# pb-led-matrix.net
KiCad netlist of a schematic drawn in EAGLE
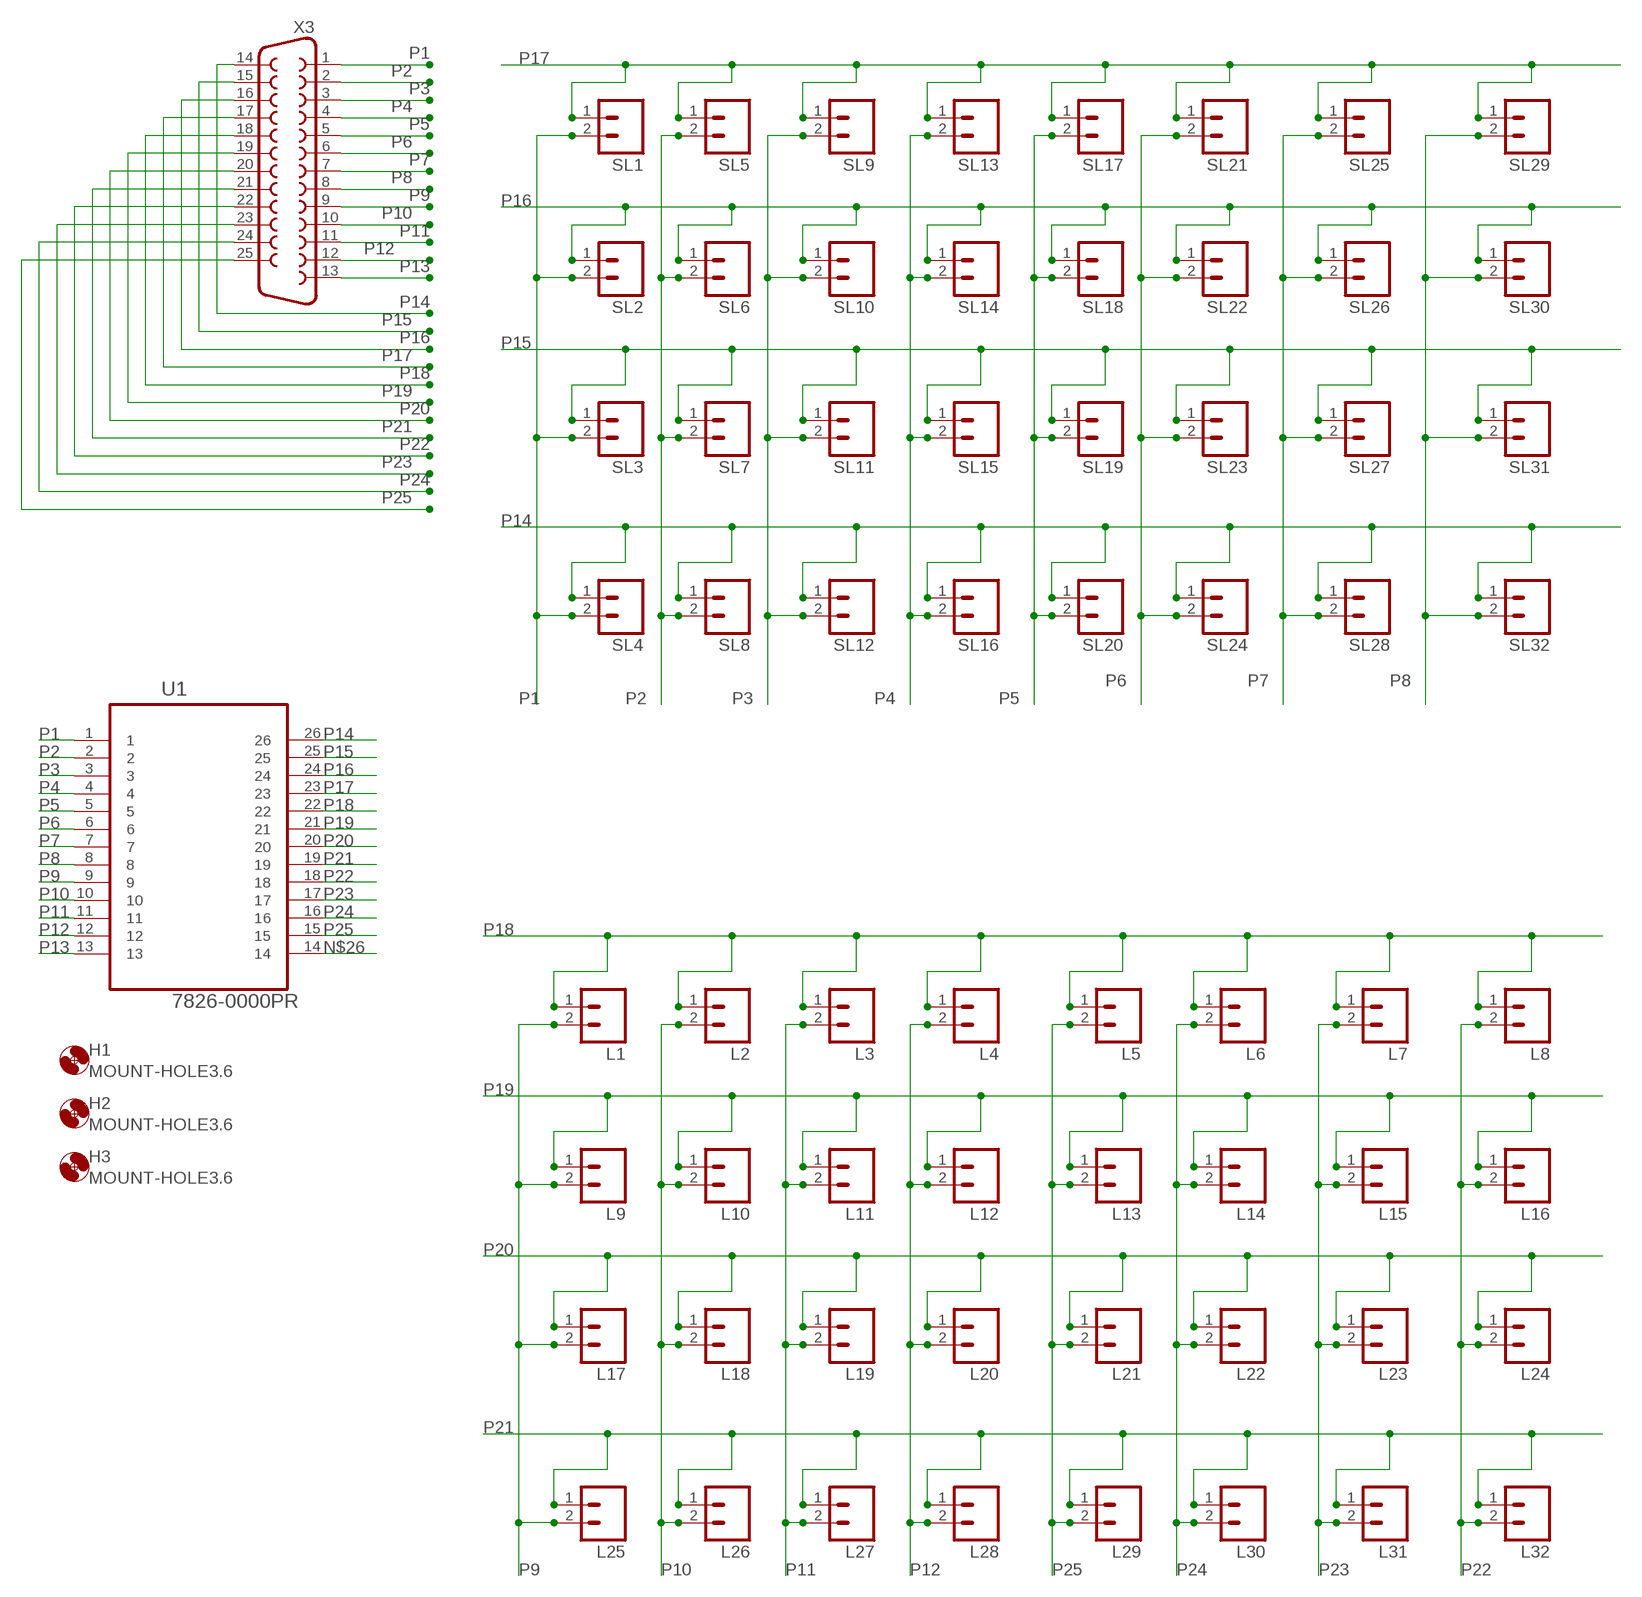
[diagram p0: schematic, sheet 1]

(export (version "E")
  (design (tool "Eeschema 10.0.6"))
  (components
    (comp (ref "H1")
      (value "MOUNT-HOLE3.6")
      (footprint "eagle-import:3,6")
      (libsource (lib "eagle-import") (part "MOUNT-HOLE3.6"))
    )
    (comp (ref "H2")
      (value "MOUNT-HOLE3.6")
      (footprint "eagle-import:3,6")
      (libsource (lib "eagle-import") (part "MOUNT-HOLE3.6"))
    )
    (comp (ref "H3")
      (value "MOUNT-HOLE3.6")
      (footprint "eagle-import:3,6")
      (libsource (lib "eagle-import") (part "MOUNT-HOLE3.6"))
    )
    (comp (ref "L1")
      (value "M02")
      (footprint "eagle-import:02P")
      (libsource (lib "eagle-import") (part "M02"))
    )
    (comp (ref "L2")
      (value "M02")
      (footprint "eagle-import:02P")
      (libsource (lib "eagle-import") (part "M02"))
    )
    (comp (ref "L3")
      (value "M02")
      (footprint "eagle-import:02P")
      (libsource (lib "eagle-import") (part "M02"))
    )
    (comp (ref "L4")
      (value "M02")
      (footprint "eagle-import:02P")
      (libsource (lib "eagle-import") (part "M02"))
    )
    (comp (ref "L5")
      (value "M02")
      (footprint "eagle-import:02P")
      (libsource (lib "eagle-import") (part "M02"))
    )
    (comp (ref "L6")
      (value "M02")
      (footprint "eagle-import:02P")
      (libsource (lib "eagle-import") (part "M02"))
    )
    (comp (ref "L7")
      (value "M02")
      (footprint "eagle-import:02P")
      (libsource (lib "eagle-import") (part "M02"))
    )
    (comp (ref "L8")
      (value "M02")
      (footprint "eagle-import:02P")
      (libsource (lib "eagle-import") (part "M02"))
    )
    (comp (ref "L9")
      (value "M02")
      (footprint "eagle-import:02P")
      (libsource (lib "eagle-import") (part "M02"))
    )
    (comp (ref "L10")
      (value "M02")
      (footprint "eagle-import:02P")
      (libsource (lib "eagle-import") (part "M02"))
    )
    (comp (ref "L11")
      (value "M02")
      (footprint "eagle-import:02P")
      (libsource (lib "eagle-import") (part "M02"))
    )
    (comp (ref "L12")
      (value "M02")
      (footprint "eagle-import:02P")
      (libsource (lib "eagle-import") (part "M02"))
    )
    (comp (ref "L13")
      (value "M02")
      (footprint "eagle-import:02P")
      (libsource (lib "eagle-import") (part "M02"))
    )
    (comp (ref "L14")
      (value "M02")
      (footprint "eagle-import:02P")
      (libsource (lib "eagle-import") (part "M02"))
    )
    (comp (ref "L15")
      (value "M02")
      (footprint "eagle-import:02P")
      (libsource (lib "eagle-import") (part "M02"))
    )
    (comp (ref "L16")
      (value "M02")
      (footprint "eagle-import:02P")
      (libsource (lib "eagle-import") (part "M02"))
    )
    (comp (ref "L17")
      (value "M02")
      (footprint "eagle-import:02P")
      (libsource (lib "eagle-import") (part "M02"))
    )
    (comp (ref "L18")
      (value "M02")
      (footprint "eagle-import:02P")
      (libsource (lib "eagle-import") (part "M02"))
    )
    (comp (ref "L19")
      (value "M02")
      (footprint "eagle-import:02P")
      (libsource (lib "eagle-import") (part "M02"))
    )
    (comp (ref "L20")
      (value "M02")
      (footprint "eagle-import:02P")
      (libsource (lib "eagle-import") (part "M02"))
    )
    (comp (ref "L21")
      (value "M02")
      (footprint "eagle-import:02P")
      (libsource (lib "eagle-import") (part "M02"))
    )
    (comp (ref "L22")
      (value "M02")
      (footprint "eagle-import:02P")
      (libsource (lib "eagle-import") (part "M02"))
    )
    (comp (ref "L23")
      (value "M02")
      (footprint "eagle-import:02P")
      (libsource (lib "eagle-import") (part "M02"))
    )
    (comp (ref "L24")
      (value "M02")
      (footprint "eagle-import:02P")
      (libsource (lib "eagle-import") (part "M02"))
    )
    (comp (ref "L25")
      (value "M02")
      (footprint "eagle-import:02P")
      (libsource (lib "eagle-import") (part "M02"))
    )
    (comp (ref "L26")
      (value "M02")
      (footprint "eagle-import:02P")
      (libsource (lib "eagle-import") (part "M02"))
    )
    (comp (ref "L27")
      (value "M02")
      (footprint "eagle-import:02P")
      (libsource (lib "eagle-import") (part "M02"))
    )
    (comp (ref "L28")
      (value "M02")
      (footprint "eagle-import:02P")
      (libsource (lib "eagle-import") (part "M02"))
    )
    (comp (ref "L29")
      (value "M02")
      (footprint "eagle-import:02P")
      (libsource (lib "eagle-import") (part "M02"))
    )
    (comp (ref "L30")
      (value "M02")
      (footprint "eagle-import:02P")
      (libsource (lib "eagle-import") (part "M02"))
    )
    (comp (ref "L31")
      (value "M02")
      (footprint "eagle-import:02P")
      (libsource (lib "eagle-import") (part "M02"))
    )
    (comp (ref "L32")
      (value "M02")
      (footprint "eagle-import:02P")
      (libsource (lib "eagle-import") (part "M02"))
    )
    (comp (ref "SL1")
      (value "M02")
      (footprint "eagle-import:02P")
      (libsource (lib "eagle-import") (part "M02"))
    )
    (comp (ref "SL2")
      (value "M02")
      (footprint "eagle-import:02P")
      (libsource (lib "eagle-import") (part "M02"))
    )
    (comp (ref "SL3")
      (value "M02")
      (footprint "eagle-import:02P")
      (libsource (lib "eagle-import") (part "M02"))
    )
    (comp (ref "SL4")
      (value "M02")
      (footprint "eagle-import:02P")
      (libsource (lib "eagle-import") (part "M02"))
    )
    (comp (ref "SL5")
      (value "M02")
      (footprint "eagle-import:02P")
      (libsource (lib "eagle-import") (part "M02"))
    )
    (comp (ref "SL6")
      (value "M02")
      (footprint "eagle-import:02P")
      (libsource (lib "eagle-import") (part "M02"))
    )
    (comp (ref "SL7")
      (value "M02")
      (footprint "eagle-import:02P")
      (libsource (lib "eagle-import") (part "M02"))
    )
    (comp (ref "SL8")
      (value "M02")
      (footprint "eagle-import:02P")
      (libsource (lib "eagle-import") (part "M02"))
    )
    (comp (ref "SL9")
      (value "M02")
      (footprint "eagle-import:02P")
      (libsource (lib "eagle-import") (part "M02"))
    )
    (comp (ref "SL10")
      (value "M02")
      (footprint "eagle-import:02P")
      (libsource (lib "eagle-import") (part "M02"))
    )
    (comp (ref "SL11")
      (value "M02")
      (footprint "eagle-import:02P")
      (libsource (lib "eagle-import") (part "M02"))
    )
    (comp (ref "SL12")
      (value "M02")
      (footprint "eagle-import:02P")
      (libsource (lib "eagle-import") (part "M02"))
    )
    (comp (ref "SL13")
      (value "M02")
      (footprint "eagle-import:02P")
      (libsource (lib "eagle-import") (part "M02"))
    )
    (comp (ref "SL14")
      (value "M02")
      (footprint "eagle-import:02P")
      (libsource (lib "eagle-import") (part "M02"))
    )
    (comp (ref "SL15")
      (value "M02")
      (footprint "eagle-import:02P")
      (libsource (lib "eagle-import") (part "M02"))
    )
    (comp (ref "SL16")
      (value "M02")
      (footprint "eagle-import:02P")
      (libsource (lib "eagle-import") (part "M02"))
    )
    (comp (ref "SL17")
      (value "M02")
      (footprint "eagle-import:02P")
      (libsource (lib "eagle-import") (part "M02"))
    )
    (comp (ref "SL18")
      (value "M02")
      (footprint "eagle-import:02P")
      (libsource (lib "eagle-import") (part "M02"))
    )
    (comp (ref "SL19")
      (value "M02")
      (footprint "eagle-import:02P")
      (libsource (lib "eagle-import") (part "M02"))
    )
    (comp (ref "SL20")
      (value "M02")
      (footprint "eagle-import:02P")
      (libsource (lib "eagle-import") (part "M02"))
    )
    (comp (ref "SL21")
      (value "M02")
      (footprint "eagle-import:02P")
      (libsource (lib "eagle-import") (part "M02"))
    )
    (comp (ref "SL22")
      (value "M02")
      (footprint "eagle-import:02P")
      (libsource (lib "eagle-import") (part "M02"))
    )
    (comp (ref "SL23")
      (value "M02")
      (footprint "eagle-import:02P")
      (libsource (lib "eagle-import") (part "M02"))
    )
    (comp (ref "SL24")
      (value "M02")
      (footprint "eagle-import:02P")
      (libsource (lib "eagle-import") (part "M02"))
    )
    (comp (ref "SL25")
      (value "M02")
      (footprint "eagle-import:02P")
      (libsource (lib "eagle-import") (part "M02"))
    )
    (comp (ref "SL26")
      (value "M02")
      (footprint "eagle-import:02P")
      (libsource (lib "eagle-import") (part "M02"))
    )
    (comp (ref "SL27")
      (value "M02")
      (footprint "eagle-import:02P")
      (libsource (lib "eagle-import") (part "M02"))
    )
    (comp (ref "SL28")
      (value "M02")
      (footprint "eagle-import:02P")
      (libsource (lib "eagle-import") (part "M02"))
    )
    (comp (ref "SL29")
      (value "M02")
      (footprint "eagle-import:02P")
      (libsource (lib "eagle-import") (part "M02"))
    )
    (comp (ref "SL30")
      (value "M02")
      (footprint "eagle-import:02P")
      (libsource (lib "eagle-import") (part "M02"))
    )
    (comp (ref "SL31")
      (value "M02")
      (footprint "eagle-import:02P")
      (libsource (lib "eagle-import") (part "M02"))
    )
    (comp (ref "SL32")
      (value "M02")
      (footprint "eagle-import:02P")
      (libsource (lib "eagle-import") (part "M02"))
    )
    (comp (ref "U1")
      (value "7826-0000PR")
      (footprint "eagle-import:3M_7826-0000PR")
      (libsource (lib "eagle-import") (part "7826-0000PR"))
    )
    (comp (ref "X3")
      (value "F25VP")
      (footprint "eagle-import:F25VP")
      (libsource (lib "eagle-import") (part "F25VP"))
    )
  )
  (nets
    (net (code "1") (name "/N$26") (class "Default")
      (node (ref "U1") (pin "14") (pinfunction "14_14") (pintype "passive"))
    )
    (net (code "2") (name "/P1") (class "Default")
      (node (ref "SL1") (pin "2") (pinfunction "2_2") (pintype "passive"))
      (node (ref "SL2") (pin "2") (pinfunction "2_2") (pintype "passive"))
      (node (ref "SL3") (pin "2") (pinfunction "2_2") (pintype "passive"))
      (node (ref "SL4") (pin "2") (pinfunction "2_2") (pintype "passive"))
      (node (ref "U1") (pin "1") (pinfunction "1_1") (pintype "passive"))
      (node (ref "X3") (pin "1") (pinfunction "1_1") (pintype "passive"))
    )
    (net (code "3") (name "/P2") (class "Default")
      (node (ref "SL5") (pin "2") (pinfunction "2_2") (pintype "passive"))
      (node (ref "SL6") (pin "2") (pinfunction "2_2") (pintype "passive"))
      (node (ref "SL7") (pin "2") (pinfunction "2_2") (pintype "passive"))
      (node (ref "SL8") (pin "2") (pinfunction "2_2") (pintype "passive"))
      (node (ref "U1") (pin "2") (pinfunction "2_2") (pintype "passive"))
      (node (ref "X3") (pin "2") (pinfunction "2_2") (pintype "passive"))
    )
    (net (code "4") (name "/P3") (class "Default")
      (node (ref "SL10") (pin "2") (pinfunction "2_2") (pintype "passive"))
      (node (ref "SL11") (pin "2") (pinfunction "2_2") (pintype "passive"))
      (node (ref "SL12") (pin "2") (pinfunction "2_2") (pintype "passive"))
      (node (ref "SL9") (pin "2") (pinfunction "2_2") (pintype "passive"))
      (node (ref "U1") (pin "3") (pinfunction "3_3") (pintype "passive"))
      (node (ref "X3") (pin "3") (pinfunction "3_3") (pintype "passive"))
    )
    (net (code "5") (name "/P4") (class "Default")
      (node (ref "SL13") (pin "2") (pinfunction "2_2") (pintype "passive"))
      (node (ref "SL14") (pin "2") (pinfunction "2_2") (pintype "passive"))
      (node (ref "SL15") (pin "2") (pinfunction "2_2") (pintype "passive"))
      (node (ref "SL16") (pin "2") (pinfunction "2_2") (pintype "passive"))
      (node (ref "U1") (pin "4") (pinfunction "4_4") (pintype "passive"))
      (node (ref "X3") (pin "4") (pinfunction "4_4") (pintype "passive"))
    )
    (net (code "6") (name "/P5") (class "Default")
      (node (ref "SL17") (pin "2") (pinfunction "2_2") (pintype "passive"))
      (node (ref "SL18") (pin "2") (pinfunction "2_2") (pintype "passive"))
      (node (ref "SL19") (pin "2") (pinfunction "2_2") (pintype "passive"))
      (node (ref "SL20") (pin "2") (pinfunction "2_2") (pintype "passive"))
      (node (ref "U1") (pin "5") (pinfunction "5_5") (pintype "passive"))
      (node (ref "X3") (pin "5") (pinfunction "5_5") (pintype "passive"))
    )
    (net (code "7") (name "/P6") (class "Default")
      (node (ref "SL21") (pin "2") (pinfunction "2_2") (pintype "passive"))
      (node (ref "SL22") (pin "2") (pinfunction "2_2") (pintype "passive"))
      (node (ref "SL23") (pin "2") (pinfunction "2_2") (pintype "passive"))
      (node (ref "SL24") (pin "2") (pinfunction "2_2") (pintype "passive"))
      (node (ref "U1") (pin "6") (pinfunction "6_6") (pintype "passive"))
      (node (ref "X3") (pin "6") (pinfunction "6_6") (pintype "passive"))
    )
    (net (code "8") (name "/P7") (class "Default")
      (node (ref "SL25") (pin "2") (pinfunction "2_2") (pintype "passive"))
      (node (ref "SL26") (pin "2") (pinfunction "2_2") (pintype "passive"))
      (node (ref "SL27") (pin "2") (pinfunction "2_2") (pintype "passive"))
      (node (ref "SL28") (pin "2") (pinfunction "2_2") (pintype "passive"))
      (node (ref "U1") (pin "7") (pinfunction "7_7") (pintype "passive"))
      (node (ref "X3") (pin "7") (pinfunction "7_7") (pintype "passive"))
    )
    (net (code "9") (name "/P8") (class "Default")
      (node (ref "SL29") (pin "2") (pinfunction "2_2") (pintype "passive"))
      (node (ref "SL30") (pin "2") (pinfunction "2_2") (pintype "passive"))
      (node (ref "SL31") (pin "2") (pinfunction "2_2") (pintype "passive"))
      (node (ref "SL32") (pin "2") (pinfunction "2_2") (pintype "passive"))
      (node (ref "U1") (pin "8") (pinfunction "8_8") (pintype "passive"))
      (node (ref "X3") (pin "8") (pinfunction "8_8") (pintype "passive"))
    )
    (net (code "10") (name "/P9") (class "Default")
      (node (ref "L1") (pin "2") (pinfunction "2_2") (pintype "passive"))
      (node (ref "L17") (pin "2") (pinfunction "2_2") (pintype "passive"))
      (node (ref "L25") (pin "2") (pinfunction "2_2") (pintype "passive"))
      (node (ref "L9") (pin "2") (pinfunction "2_2") (pintype "passive"))
      (node (ref "U1") (pin "9") (pinfunction "9_9") (pintype "passive"))
      (node (ref "X3") (pin "9") (pinfunction "9_9") (pintype "passive"))
    )
    (net (code "11") (name "/P10") (class "Default")
      (node (ref "L10") (pin "2") (pinfunction "2_2") (pintype "passive"))
      (node (ref "L18") (pin "2") (pinfunction "2_2") (pintype "passive"))
      (node (ref "L2") (pin "2") (pinfunction "2_2") (pintype "passive"))
      (node (ref "L26") (pin "2") (pinfunction "2_2") (pintype "passive"))
      (node (ref "U1") (pin "10") (pinfunction "10_10") (pintype "passive"))
      (node (ref "X3") (pin "10") (pinfunction "10_10") (pintype "passive"))
    )
    (net (code "12") (name "/P11") (class "Default")
      (node (ref "L11") (pin "2") (pinfunction "2_2") (pintype "passive"))
      (node (ref "L19") (pin "2") (pinfunction "2_2") (pintype "passive"))
      (node (ref "L27") (pin "2") (pinfunction "2_2") (pintype "passive"))
      (node (ref "L3") (pin "2") (pinfunction "2_2") (pintype "passive"))
      (node (ref "U1") (pin "11") (pinfunction "11_11") (pintype "passive"))
      (node (ref "X3") (pin "11") (pinfunction "11_11") (pintype "passive"))
    )
    (net (code "13") (name "/P12") (class "Default")
      (node (ref "L12") (pin "2") (pinfunction "2_2") (pintype "passive"))
      (node (ref "L20") (pin "2") (pinfunction "2_2") (pintype "passive"))
      (node (ref "L28") (pin "2") (pinfunction "2_2") (pintype "passive"))
      (node (ref "L4") (pin "2") (pinfunction "2_2") (pintype "passive"))
      (node (ref "U1") (pin "12") (pinfunction "12_12") (pintype "passive"))
      (node (ref "X3") (pin "12") (pinfunction "12_12") (pintype "passive"))
    )
    (net (code "14") (name "/P13") (class "Default")
      (node (ref "U1") (pin "13") (pinfunction "13_13") (pintype "passive"))
      (node (ref "X3") (pin "13") (pinfunction "13_13") (pintype "passive"))
    )
    (net (code "15") (name "/P14") (class "Default")
      (node (ref "SL12") (pin "1") (pinfunction "1_1") (pintype "passive"))
      (node (ref "SL16") (pin "1") (pinfunction "1_1") (pintype "passive"))
      (node (ref "SL20") (pin "1") (pinfunction "1_1") (pintype "passive"))
      (node (ref "SL24") (pin "1") (pinfunction "1_1") (pintype "passive"))
      (node (ref "SL28") (pin "1") (pinfunction "1_1") (pintype "passive"))
      (node (ref "SL32") (pin "1") (pinfunction "1_1") (pintype "passive"))
      (node (ref "SL4") (pin "1") (pinfunction "1_1") (pintype "passive"))
      (node (ref "SL8") (pin "1") (pinfunction "1_1") (pintype "passive"))
      (node (ref "U1") (pin "26") (pinfunction "26_26") (pintype "passive"))
      (node (ref "X3") (pin "14") (pinfunction "14_14") (pintype "passive"))
    )
    (net (code "16") (name "/P15") (class "Default")
      (node (ref "SL11") (pin "1") (pinfunction "1_1") (pintype "passive"))
      (node (ref "SL15") (pin "1") (pinfunction "1_1") (pintype "passive"))
      (node (ref "SL19") (pin "1") (pinfunction "1_1") (pintype "passive"))
      (node (ref "SL23") (pin "1") (pinfunction "1_1") (pintype "passive"))
      (node (ref "SL27") (pin "1") (pinfunction "1_1") (pintype "passive"))
      (node (ref "SL3") (pin "1") (pinfunction "1_1") (pintype "passive"))
      (node (ref "SL31") (pin "1") (pinfunction "1_1") (pintype "passive"))
      (node (ref "SL7") (pin "1") (pinfunction "1_1") (pintype "passive"))
      (node (ref "U1") (pin "25") (pinfunction "25_25") (pintype "passive"))
      (node (ref "X3") (pin "15") (pinfunction "15_15") (pintype "passive"))
    )
    (net (code "17") (name "/P16") (class "Default")
      (node (ref "SL10") (pin "1") (pinfunction "1_1") (pintype "passive"))
      (node (ref "SL14") (pin "1") (pinfunction "1_1") (pintype "passive"))
      (node (ref "SL18") (pin "1") (pinfunction "1_1") (pintype "passive"))
      (node (ref "SL2") (pin "1") (pinfunction "1_1") (pintype "passive"))
      (node (ref "SL22") (pin "1") (pinfunction "1_1") (pintype "passive"))
      (node (ref "SL26") (pin "1") (pinfunction "1_1") (pintype "passive"))
      (node (ref "SL30") (pin "1") (pinfunction "1_1") (pintype "passive"))
      (node (ref "SL6") (pin "1") (pinfunction "1_1") (pintype "passive"))
      (node (ref "U1") (pin "24") (pinfunction "24_24") (pintype "passive"))
      (node (ref "X3") (pin "16") (pinfunction "16_16") (pintype "passive"))
    )
    (net (code "18") (name "/P17") (class "Default")
      (node (ref "SL1") (pin "1") (pinfunction "1_1") (pintype "passive"))
      (node (ref "SL13") (pin "1") (pinfunction "1_1") (pintype "passive"))
      (node (ref "SL17") (pin "1") (pinfunction "1_1") (pintype "passive"))
      (node (ref "SL21") (pin "1") (pinfunction "1_1") (pintype "passive"))
      (node (ref "SL25") (pin "1") (pinfunction "1_1") (pintype "passive"))
      (node (ref "SL29") (pin "1") (pinfunction "1_1") (pintype "passive"))
      (node (ref "SL5") (pin "1") (pinfunction "1_1") (pintype "passive"))
      (node (ref "SL9") (pin "1") (pinfunction "1_1") (pintype "passive"))
      (node (ref "U1") (pin "23") (pinfunction "23_23") (pintype "passive"))
      (node (ref "X3") (pin "17") (pinfunction "17_17") (pintype "passive"))
    )
    (net (code "19") (name "/P18") (class "Default")
      (node (ref "L1") (pin "1") (pinfunction "1_1") (pintype "passive"))
      (node (ref "L2") (pin "1") (pinfunction "1_1") (pintype "passive"))
      (node (ref "L3") (pin "1") (pinfunction "1_1") (pintype "passive"))
      (node (ref "L4") (pin "1") (pinfunction "1_1") (pintype "passive"))
      (node (ref "L5") (pin "1") (pinfunction "1_1") (pintype "passive"))
      (node (ref "L6") (pin "1") (pinfunction "1_1") (pintype "passive"))
      (node (ref "L7") (pin "1") (pinfunction "1_1") (pintype "passive"))
      (node (ref "L8") (pin "1") (pinfunction "1_1") (pintype "passive"))
      (node (ref "U1") (pin "22") (pinfunction "22_22") (pintype "passive"))
      (node (ref "X3") (pin "18") (pinfunction "18_18") (pintype "passive"))
    )
    (net (code "20") (name "/P19") (class "Default")
      (node (ref "L10") (pin "1") (pinfunction "1_1") (pintype "passive"))
      (node (ref "L11") (pin "1") (pinfunction "1_1") (pintype "passive"))
      (node (ref "L12") (pin "1") (pinfunction "1_1") (pintype "passive"))
      (node (ref "L13") (pin "1") (pinfunction "1_1") (pintype "passive"))
      (node (ref "L14") (pin "1") (pinfunction "1_1") (pintype "passive"))
      (node (ref "L15") (pin "1") (pinfunction "1_1") (pintype "passive"))
      (node (ref "L16") (pin "1") (pinfunction "1_1") (pintype "passive"))
      (node (ref "L9") (pin "1") (pinfunction "1_1") (pintype "passive"))
      (node (ref "U1") (pin "21") (pinfunction "21_21") (pintype "passive"))
      (node (ref "X3") (pin "19") (pinfunction "19_19") (pintype "passive"))
    )
    (net (code "21") (name "/P20") (class "Default")
      (node (ref "L17") (pin "1") (pinfunction "1_1") (pintype "passive"))
      (node (ref "L18") (pin "1") (pinfunction "1_1") (pintype "passive"))
      (node (ref "L19") (pin "1") (pinfunction "1_1") (pintype "passive"))
      (node (ref "L20") (pin "1") (pinfunction "1_1") (pintype "passive"))
      (node (ref "L21") (pin "1") (pinfunction "1_1") (pintype "passive"))
      (node (ref "L22") (pin "1") (pinfunction "1_1") (pintype "passive"))
      (node (ref "L23") (pin "1") (pinfunction "1_1") (pintype "passive"))
      (node (ref "L24") (pin "1") (pinfunction "1_1") (pintype "passive"))
      (node (ref "U1") (pin "20") (pinfunction "20_20") (pintype "passive"))
      (node (ref "X3") (pin "20") (pinfunction "20_20") (pintype "passive"))
    )
    (net (code "22") (name "/P21") (class "Default")
      (node (ref "L25") (pin "1") (pinfunction "1_1") (pintype "passive"))
      (node (ref "L26") (pin "1") (pinfunction "1_1") (pintype "passive"))
      (node (ref "L27") (pin "1") (pinfunction "1_1") (pintype "passive"))
      (node (ref "L28") (pin "1") (pinfunction "1_1") (pintype "passive"))
      (node (ref "L29") (pin "1") (pinfunction "1_1") (pintype "passive"))
      (node (ref "L30") (pin "1") (pinfunction "1_1") (pintype "passive"))
      (node (ref "L31") (pin "1") (pinfunction "1_1") (pintype "passive"))
      (node (ref "L32") (pin "1") (pinfunction "1_1") (pintype "passive"))
      (node (ref "U1") (pin "19") (pinfunction "19_19") (pintype "passive"))
      (node (ref "X3") (pin "21") (pinfunction "21_21") (pintype "passive"))
    )
    (net (code "23") (name "/P22") (class "Default")
      (node (ref "L16") (pin "2") (pinfunction "2_2") (pintype "passive"))
      (node (ref "L24") (pin "2") (pinfunction "2_2") (pintype "passive"))
      (node (ref "L32") (pin "2") (pinfunction "2_2") (pintype "passive"))
      (node (ref "L8") (pin "2") (pinfunction "2_2") (pintype "passive"))
      (node (ref "U1") (pin "18") (pinfunction "18_18") (pintype "passive"))
      (node (ref "X3") (pin "22") (pinfunction "22_22") (pintype "passive"))
    )
    (net (code "24") (name "/P23") (class "Default")
      (node (ref "L15") (pin "2") (pinfunction "2_2") (pintype "passive"))
      (node (ref "L23") (pin "2") (pinfunction "2_2") (pintype "passive"))
      (node (ref "L31") (pin "2") (pinfunction "2_2") (pintype "passive"))
      (node (ref "L7") (pin "2") (pinfunction "2_2") (pintype "passive"))
      (node (ref "U1") (pin "17") (pinfunction "17_17") (pintype "passive"))
      (node (ref "X3") (pin "23") (pinfunction "23_23") (pintype "passive"))
    )
    (net (code "25") (name "/P24") (class "Default")
      (node (ref "L14") (pin "2") (pinfunction "2_2") (pintype "passive"))
      (node (ref "L22") (pin "2") (pinfunction "2_2") (pintype "passive"))
      (node (ref "L30") (pin "2") (pinfunction "2_2") (pintype "passive"))
      (node (ref "L6") (pin "2") (pinfunction "2_2") (pintype "passive"))
      (node (ref "U1") (pin "16") (pinfunction "16_16") (pintype "passive"))
      (node (ref "X3") (pin "24") (pinfunction "24_24") (pintype "passive"))
    )
    (net (code "26") (name "/P25") (class "Default")
      (node (ref "L13") (pin "2") (pinfunction "2_2") (pintype "passive"))
      (node (ref "L21") (pin "2") (pinfunction "2_2") (pintype "passive"))
      (node (ref "L29") (pin "2") (pinfunction "2_2") (pintype "passive"))
      (node (ref "L5") (pin "2") (pinfunction "2_2") (pintype "passive"))
      (node (ref "U1") (pin "15") (pinfunction "15_15") (pintype "passive"))
      (node (ref "X3") (pin "25") (pinfunction "25_25") (pintype "passive"))
    )
  )
)
